# 12_DDR2.net
KiCad netlist of a schematic drawn in Altium Designer
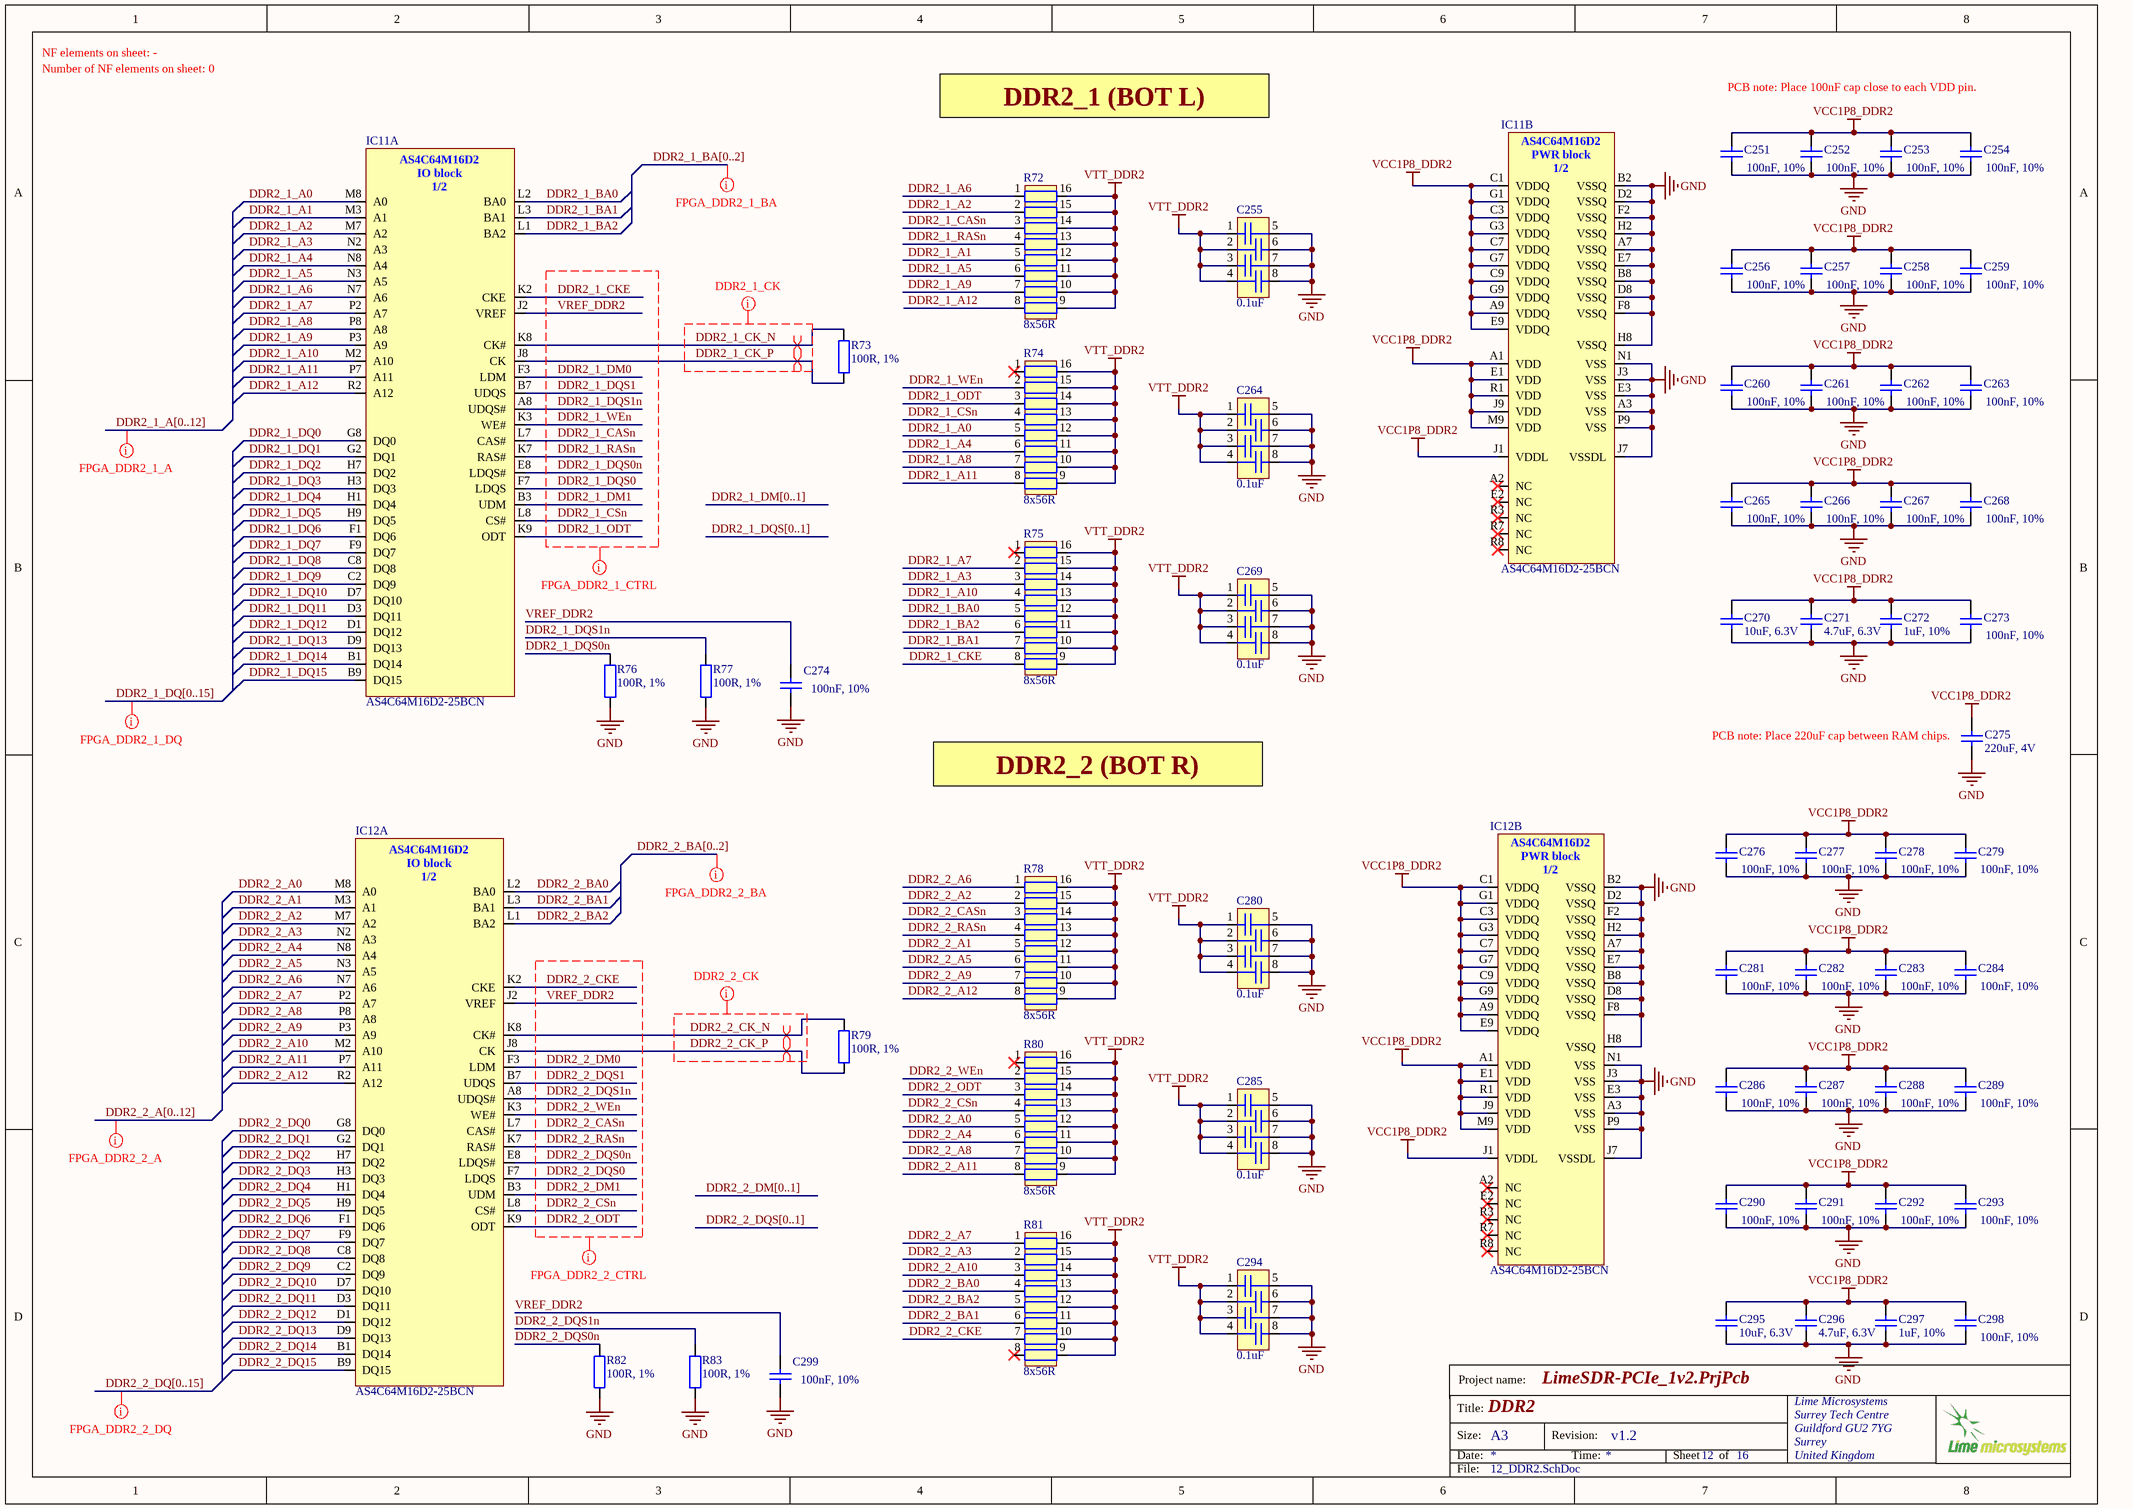
[diagram p0: 12_DDR2.SchDoc]

(export (version "E")
  (design (tool "Eeschema 10.0.6"))
  (components
    (comp (ref "C251")
      (value "100nF, 10%")
      (footprint "CAP0402")
      (fields
        (field (name "TOLERANCE") "10 %")
        (field (name "MANUFACTURER") "Murata Electronics")
        (field (name "MANUFACTURER PART NUMBER") "GRM155R71C104KA88D")
      )
      (libsource (lib "LimeFPGAboard_schLib") (part "Cap_0603"))
    )
    (comp (ref "C252")
      (value "100nF, 10%")
      (footprint "CAP0402")
      (fields
        (field (name "TOLERANCE") "10 %")
        (field (name "MANUFACTURER") "Murata Electronics")
        (field (name "MANUFACTURER PART NUMBER") "GRM155R71C104KA88D")
      )
      (libsource (lib "LimeFPGAboard_schLib") (part "Cap_0603"))
    )
    (comp (ref "C253")
      (value "100nF, 10%")
      (footprint "CAP0402")
      (fields
        (field (name "TOLERANCE") "10 %")
        (field (name "MANUFACTURER") "Murata Electronics")
        (field (name "MANUFACTURER PART NUMBER") "GRM155R71C104KA88D")
      )
      (libsource (lib "LimeFPGAboard_schLib") (part "Cap_0603"))
    )
    (comp (ref "C254")
      (value "100nF, 10%")
      (footprint "CAP0402")
      (fields
        (field (name "TOLERANCE") "10 %")
        (field (name "MANUFACTURER") "Murata Electronics")
        (field (name "MANUFACTURER PART NUMBER") "GRM155R71C104KA88D")
      )
      (libsource (lib "LimeFPGAboard_schLib") (part "Cap_0603"))
    )
    (comp (ref "C255")
      (value "0.1uF")
      (footprint "CKCA43X7R1C104M100AA")
      (fields (field (name "MANUFACTURER") "TDK") (field (name "TOLERANCE") "20 %"))
      (libsource (lib "LimeFPGAboard_schLib") (part "4X_cap_array_1206"))
    )
    (comp (ref "C256")
      (value "100nF, 10%")
      (footprint "CAP0402")
      (fields
        (field (name "TOLERANCE") "10 %")
        (field (name "MANUFACTURER") "Murata Electronics")
        (field (name "MANUFACTURER PART NUMBER") "GRM155R71C104KA88D")
      )
      (libsource (lib "LimeFPGAboard_schLib") (part "Cap_0603"))
    )
    (comp (ref "C257")
      (value "100nF, 10%")
      (footprint "CAP0402")
      (fields
        (field (name "TOLERANCE") "10 %")
        (field (name "MANUFACTURER") "Murata Electronics")
        (field (name "MANUFACTURER PART NUMBER") "GRM155R71C104KA88D")
      )
      (libsource (lib "LimeFPGAboard_schLib") (part "Cap_0603"))
    )
    (comp (ref "C258")
      (value "100nF, 10%")
      (footprint "CAP0402")
      (fields
        (field (name "TOLERANCE") "10 %")
        (field (name "MANUFACTURER") "Murata Electronics")
        (field (name "MANUFACTURER PART NUMBER") "GRM155R71C104KA88D")
      )
      (libsource (lib "LimeFPGAboard_schLib") (part "Cap_0603"))
    )
    (comp (ref "C259")
      (value "100nF, 10%")
      (footprint "CAP0402")
      (fields
        (field (name "TOLERANCE") "10 %")
        (field (name "MANUFACTURER") "Murata Electronics")
        (field (name "MANUFACTURER PART NUMBER") "GRM155R71C104KA88D")
      )
      (libsource (lib "LimeFPGAboard_schLib") (part "Cap_0603"))
    )
    (comp (ref "C260")
      (value "100nF, 10%")
      (footprint "CAP0402")
      (fields
        (field (name "TOLERANCE") "10 %")
        (field (name "MANUFACTURER") "Murata Electronics")
        (field (name "MANUFACTURER PART NUMBER") "GRM155R71C104KA88D")
      )
      (libsource (lib "LimeFPGAboard_schLib") (part "Cap_0603"))
    )
    (comp (ref "C261")
      (value "100nF, 10%")
      (footprint "CAP0402")
      (fields
        (field (name "TOLERANCE") "10 %")
        (field (name "MANUFACTURER") "Murata Electronics")
        (field (name "MANUFACTURER PART NUMBER") "GRM155R71C104KA88D")
      )
      (libsource (lib "LimeFPGAboard_schLib") (part "Cap_0603"))
    )
    (comp (ref "C262")
      (value "100nF, 10%")
      (footprint "CAP0402")
      (fields
        (field (name "TOLERANCE") "10 %")
        (field (name "MANUFACTURER") "Murata Electronics")
        (field (name "MANUFACTURER PART NUMBER") "GRM155R71C104KA88D")
      )
      (libsource (lib "LimeFPGAboard_schLib") (part "Cap_0603"))
    )
    (comp (ref "C263")
      (value "100nF, 10%")
      (footprint "CAP0402")
      (fields
        (field (name "TOLERANCE") "10 %")
        (field (name "MANUFACTURER") "Murata Electronics")
        (field (name "MANUFACTURER PART NUMBER") "GRM155R71C104KA88D")
      )
      (libsource (lib "LimeFPGAboard_schLib") (part "Cap_0603"))
    )
    (comp (ref "C264")
      (value "0.1uF")
      (footprint "CKCA43X7R1C104M100AA")
      (fields (field (name "MANUFACTURER") "TDK") (field (name "TOLERANCE") "20 %"))
      (libsource (lib "LimeFPGAboard_schLib") (part "4X_cap_array_1206"))
    )
    (comp (ref "C265")
      (value "100nF, 10%")
      (footprint "CAP0402")
      (fields
        (field (name "TOLERANCE") "10 %")
        (field (name "MANUFACTURER") "Murata Electronics")
        (field (name "MANUFACTURER PART NUMBER") "GRM155R71C104KA88D")
      )
      (libsource (lib "LimeFPGAboard_schLib") (part "Cap_0603"))
    )
    (comp (ref "C266")
      (value "100nF, 10%")
      (footprint "CAP0402")
      (fields
        (field (name "TOLERANCE") "10 %")
        (field (name "MANUFACTURER") "Murata Electronics")
        (field (name "MANUFACTURER PART NUMBER") "GRM155R71C104KA88D")
      )
      (libsource (lib "LimeFPGAboard_schLib") (part "Cap_0603"))
    )
    (comp (ref "C267")
      (value "100nF, 10%")
      (footprint "CAP0402")
      (fields
        (field (name "TOLERANCE") "10 %")
        (field (name "MANUFACTURER") "Murata Electronics")
        (field (name "MANUFACTURER PART NUMBER") "GRM155R71C104KA88D")
      )
      (libsource (lib "LimeFPGAboard_schLib") (part "Cap_0603"))
    )
    (comp (ref "C268")
      (value "100nF, 10%")
      (footprint "CAP0402")
      (fields
        (field (name "TOLERANCE") "10 %")
        (field (name "MANUFACTURER") "Murata Electronics")
        (field (name "MANUFACTURER PART NUMBER") "GRM155R71C104KA88D")
      )
      (libsource (lib "LimeFPGAboard_schLib") (part "Cap_0603"))
    )
    (comp (ref "C269")
      (value "0.1uF")
      (footprint "CKCA43X7R1C104M100AA")
      (fields (field (name "MANUFACTURER") "TDK") (field (name "TOLERANCE") "20 %"))
      (libsource (lib "LimeFPGAboard_schLib") (part "4X_cap_array_1206"))
    )
    (comp (ref "C270")
      (value "10uF, 6.3V")
      (footprint "CAP0603")
      (fields (field (name "TOLERANCE") "±20%") (field (name "MANUFACTURER") "Yageo"))
      (libsource (lib "LimeFPGAboard_schLib") (part "Cap_0603"))
    )
    (comp (ref "C271")
      (value "4.7uF, 6.3V")
      (footprint "CAP0402")
      (fields
        (field (name "MANUFACTURER") "Murata Electronics North America")
        (field (name "TOLERANCE") "±20%")
      )
      (libsource (lib "LimeMicroAltiumLib_schLib") (part "Cap_0402"))
    )
    (comp (ref "C272")
      (value "1uF, 10%")
      (footprint "CAP0402")
      (fields (field (name "MANUFACTURER") "TDK"))
      (libsource (lib "LimeMicroAltiumLib_schLib") (part "Cap_0402"))
    )
    (comp (ref "C273")
      (value "100nF, 10%")
      (footprint "CAP0402")
      (fields
        (field (name "TOLERANCE") "10 %")
        (field (name "MANUFACTURER") "Murata Electronics")
        (field (name "MANUFACTURER PART NUMBER") "GRM155R71C104KA88D")
      )
      (libsource (lib "LimeFPGAboard_schLib") (part "Cap_0603"))
    )
    (comp (ref "C274")
      (value "100nF, 10%")
      (footprint "CAP0402")
      (fields
        (field (name "TOLERANCE") "10 %")
        (field (name "MANUFACTURER") "Murata Electronics")
        (field (name "MANUFACTURER PART NUMBER") "GRM155R71C104KA88D")
      )
      (libsource (lib "LimeFPGAboard_schLib") (part "Cap_0603"))
    )
    (comp (ref "C275")
      (value "220uF, 4V")
      (footprint "CAP1206")
      (fields
        (field (name "MANUFACTURER PART NUMBER") "GRM31CR60G227ME11L")
        (field (name "MANUFACTURER") "Murata Electronics North America")
        (field (name "TOLERANCE") "±20%")
      )
      (libsource (lib "LimeFPGAboard_schLib") (part "Cap_1206"))
    )
    (comp (ref "C276")
      (value "100nF, 10%")
      (footprint "CAP0402")
      (fields
        (field (name "TOLERANCE") "10 %")
        (field (name "MANUFACTURER") "Murata Electronics")
        (field (name "MANUFACTURER PART NUMBER") "GRM155R71C104KA88D")
      )
      (libsource (lib "LimeFPGAboard_schLib") (part "Cap_0603"))
    )
    (comp (ref "C277")
      (value "100nF, 10%")
      (footprint "CAP0402")
      (fields
        (field (name "TOLERANCE") "10 %")
        (field (name "MANUFACTURER") "Murata Electronics")
        (field (name "MANUFACTURER PART NUMBER") "GRM155R71C104KA88D")
      )
      (libsource (lib "LimeFPGAboard_schLib") (part "Cap_0603"))
    )
    (comp (ref "C278")
      (value "100nF, 10%")
      (footprint "CAP0402")
      (fields
        (field (name "TOLERANCE") "10 %")
        (field (name "MANUFACTURER") "Murata Electronics")
        (field (name "MANUFACTURER PART NUMBER") "GRM155R71C104KA88D")
      )
      (libsource (lib "LimeFPGAboard_schLib") (part "Cap_0603"))
    )
    (comp (ref "C279")
      (value "100nF, 10%")
      (footprint "CAP0402")
      (fields
        (field (name "TOLERANCE") "10 %")
        (field (name "MANUFACTURER") "Murata Electronics")
        (field (name "MANUFACTURER PART NUMBER") "GRM155R71C104KA88D")
      )
      (libsource (lib "LimeFPGAboard_schLib") (part "Cap_0603"))
    )
    (comp (ref "C280")
      (value "0.1uF")
      (footprint "CKCA43X7R1C104M100AA")
      (fields (field (name "MANUFACTURER") "TDK") (field (name "TOLERANCE") "20 %"))
      (libsource (lib "LimeFPGAboard_schLib") (part "4X_cap_array_1206"))
    )
    (comp (ref "C281")
      (value "100nF, 10%")
      (footprint "CAP0402")
      (fields
        (field (name "TOLERANCE") "10 %")
        (field (name "MANUFACTURER") "Murata Electronics")
        (field (name "MANUFACTURER PART NUMBER") "GRM155R71C104KA88D")
      )
      (libsource (lib "LimeFPGAboard_schLib") (part "Cap_0603"))
    )
    (comp (ref "C282")
      (value "100nF, 10%")
      (footprint "CAP0402")
      (fields
        (field (name "TOLERANCE") "10 %")
        (field (name "MANUFACTURER") "Murata Electronics")
        (field (name "MANUFACTURER PART NUMBER") "GRM155R71C104KA88D")
      )
      (libsource (lib "LimeFPGAboard_schLib") (part "Cap_0603"))
    )
    (comp (ref "C283")
      (value "100nF, 10%")
      (footprint "CAP0402")
      (fields
        (field (name "TOLERANCE") "10 %")
        (field (name "MANUFACTURER") "Murata Electronics")
        (field (name "MANUFACTURER PART NUMBER") "GRM155R71C104KA88D")
      )
      (libsource (lib "LimeFPGAboard_schLib") (part "Cap_0603"))
    )
    (comp (ref "C284")
      (value "100nF, 10%")
      (footprint "CAP0402")
      (fields
        (field (name "TOLERANCE") "10 %")
        (field (name "MANUFACTURER") "Murata Electronics")
        (field (name "MANUFACTURER PART NUMBER") "GRM155R71C104KA88D")
      )
      (libsource (lib "LimeFPGAboard_schLib") (part "Cap_0603"))
    )
    (comp (ref "C285")
      (value "0.1uF")
      (footprint "CKCA43X7R1C104M100AA")
      (fields (field (name "MANUFACTURER") "TDK") (field (name "TOLERANCE") "20 %"))
      (libsource (lib "LimeFPGAboard_schLib") (part "4X_cap_array_1206"))
    )
    (comp (ref "C286")
      (value "100nF, 10%")
      (footprint "CAP0402")
      (fields
        (field (name "TOLERANCE") "10 %")
        (field (name "MANUFACTURER") "Murata Electronics")
        (field (name "MANUFACTURER PART NUMBER") "GRM155R71C104KA88D")
      )
      (libsource (lib "LimeFPGAboard_schLib") (part "Cap_0603"))
    )
    (comp (ref "C287")
      (value "100nF, 10%")
      (footprint "CAP0402")
      (fields
        (field (name "TOLERANCE") "10 %")
        (field (name "MANUFACTURER") "Murata Electronics")
        (field (name "MANUFACTURER PART NUMBER") "GRM155R71C104KA88D")
      )
      (libsource (lib "LimeFPGAboard_schLib") (part "Cap_0603"))
    )
    (comp (ref "C288")
      (value "100nF, 10%")
      (footprint "CAP0402")
      (fields
        (field (name "TOLERANCE") "10 %")
        (field (name "MANUFACTURER") "Murata Electronics")
        (field (name "MANUFACTURER PART NUMBER") "GRM155R71C104KA88D")
      )
      (libsource (lib "LimeFPGAboard_schLib") (part "Cap_0603"))
    )
    (comp (ref "C289")
      (value "100nF, 10%")
      (footprint "CAP0402")
      (fields
        (field (name "TOLERANCE") "10 %")
        (field (name "MANUFACTURER") "Murata Electronics")
        (field (name "MANUFACTURER PART NUMBER") "GRM155R71C104KA88D")
      )
      (libsource (lib "LimeFPGAboard_schLib") (part "Cap_0603"))
    )
    (comp (ref "C290")
      (value "100nF, 10%")
      (footprint "CAP0402")
      (fields
        (field (name "TOLERANCE") "10 %")
        (field (name "MANUFACTURER") "Murata Electronics")
        (field (name "MANUFACTURER PART NUMBER") "GRM155R71C104KA88D")
      )
      (libsource (lib "LimeFPGAboard_schLib") (part "Cap_0603"))
    )
    (comp (ref "C291")
      (value "100nF, 10%")
      (footprint "CAP0402")
      (fields
        (field (name "TOLERANCE") "10 %")
        (field (name "MANUFACTURER") "Murata Electronics")
        (field (name "MANUFACTURER PART NUMBER") "GRM155R71C104KA88D")
      )
      (libsource (lib "LimeFPGAboard_schLib") (part "Cap_0603"))
    )
    (comp (ref "C292")
      (value "100nF, 10%")
      (footprint "CAP0402")
      (fields
        (field (name "TOLERANCE") "10 %")
        (field (name "MANUFACTURER") "Murata Electronics")
        (field (name "MANUFACTURER PART NUMBER") "GRM155R71C104KA88D")
      )
      (libsource (lib "LimeFPGAboard_schLib") (part "Cap_0603"))
    )
    (comp (ref "C293")
      (value "100nF, 10%")
      (footprint "CAP0402")
      (fields
        (field (name "TOLERANCE") "10 %")
        (field (name "MANUFACTURER") "Murata Electronics")
        (field (name "MANUFACTURER PART NUMBER") "GRM155R71C104KA88D")
      )
      (libsource (lib "LimeFPGAboard_schLib") (part "Cap_0603"))
    )
    (comp (ref "C294")
      (value "0.1uF")
      (footprint "CKCA43X7R1C104M100AA")
      (fields (field (name "MANUFACTURER") "TDK") (field (name "TOLERANCE") "20 %"))
      (libsource (lib "LimeFPGAboard_schLib") (part "4X_cap_array_1206"))
    )
    (comp (ref "C295")
      (value "10uF, 6.3V")
      (footprint "CAP0603")
      (fields (field (name "TOLERANCE") "±20%") (field (name "MANUFACTURER") "Yageo"))
      (libsource (lib "LimeFPGAboard_schLib") (part "Cap_0603"))
    )
    (comp (ref "C296")
      (value "4.7uF, 6.3V")
      (footprint "CAP0402")
      (fields
        (field (name "MANUFACTURER") "Murata Electronics North America")
        (field (name "TOLERANCE") "±20%")
      )
      (libsource (lib "LimeMicroAltiumLib_schLib") (part "Cap_0402"))
    )
    (comp (ref "C297")
      (value "1uF, 10%")
      (footprint "CAP0402")
      (fields (field (name "MANUFACTURER") "TDK"))
      (libsource (lib "LimeMicroAltiumLib_schLib") (part "Cap_0402"))
    )
    (comp (ref "C298")
      (value "100nF, 10%")
      (footprint "CAP0402")
      (fields
        (field (name "TOLERANCE") "10 %")
        (field (name "MANUFACTURER") "Murata Electronics")
        (field (name "MANUFACTURER PART NUMBER") "GRM155R71C104KA88D")
      )
      (libsource (lib "LimeFPGAboard_schLib") (part "Cap_0603"))
    )
    (comp (ref "C299")
      (value "100nF, 10%")
      (footprint "CAP0402")
      (fields
        (field (name "TOLERANCE") "10 %")
        (field (name "MANUFACTURER") "Murata Electronics")
        (field (name "MANUFACTURER PART NUMBER") "GRM155R71C104KA88D")
      )
      (libsource (lib "LimeFPGAboard_schLib") (part "Cap_0603"))
    )
    (comp (ref "IC11")
      (value "AS4C64M16D2-25BCN")
      (footprint "AS4C64M16D2")
      (fields (field (name "MANUFACTURER") "Alliance Memory, Inc."))
      (libsource (lib "LimeMicroAltiumLib_schLib") (part "AS4C64M16D2-25BCN"))
    )
    (comp (ref "IC12")
      (value "AS4C64M16D2-25BCN")
      (footprint "AS4C64M16D2")
      (fields (field (name "MANUFACTURER") "Alliance Memory, Inc."))
      (libsource (lib "LimeMicroAltiumLib_schLib") (part "AS4C64M16D2-25BCN"))
    )
    (comp (ref "R72")
      (value "8x56R")
      (footprint "EXB2HV")
      (fields (field (name "MANUFACTURER") "PANASONIC ELECTRONIC COMPONENTS"))
      (libsource (lib "LimeFPGAboard_schLib") (part "8X_resistor_array_0402"))
    )
    (comp (ref "R73")
      (value "100R, 1%")
      (footprint "RES0402")
      (fields (field (name "TOLERANCE") "±1%") (field (name "MANUFACTURER") "Stackpole Electronics Inc."))
      (libsource (lib "LimeFPGAboard_schLib") (part "Res_0402"))
    )
    (comp (ref "R74")
      (value "8x56R")
      (footprint "EXB2HV")
      (fields (field (name "MANUFACTURER") "PANASONIC ELECTRONIC COMPONENTS"))
      (libsource (lib "LimeFPGAboard_schLib") (part "8X_resistor_array_0402"))
    )
    (comp (ref "R75")
      (value "8x56R")
      (footprint "EXB2HV")
      (fields (field (name "MANUFACTURER") "PANASONIC ELECTRONIC COMPONENTS"))
      (libsource (lib "LimeFPGAboard_schLib") (part "8X_resistor_array_0402"))
    )
    (comp (ref "R76")
      (value "100R, 1%")
      (footprint "RES0402")
      (fields (field (name "TOLERANCE") "±1%") (field (name "MANUFACTURER") "Stackpole Electronics Inc."))
      (libsource (lib "LimeFPGAboard_schLib") (part "Res_0402"))
    )
    (comp (ref "R77")
      (value "100R, 1%")
      (footprint "RES0402")
      (fields (field (name "TOLERANCE") "±1%") (field (name "MANUFACTURER") "Stackpole Electronics Inc."))
      (libsource (lib "LimeFPGAboard_schLib") (part "Res_0402"))
    )
    (comp (ref "R78")
      (value "8x56R")
      (footprint "EXB2HV")
      (fields (field (name "MANUFACTURER") "PANASONIC ELECTRONIC COMPONENTS"))
      (libsource (lib "LimeFPGAboard_schLib") (part "8X_resistor_array_0402"))
    )
    (comp (ref "R79")
      (value "100R, 1%")
      (footprint "RES0402")
      (fields (field (name "TOLERANCE") "±1%") (field (name "MANUFACTURER") "Stackpole Electronics Inc."))
      (libsource (lib "LimeFPGAboard_schLib") (part "Res_0402"))
    )
    (comp (ref "R80")
      (value "8x56R")
      (footprint "EXB2HV")
      (fields (field (name "MANUFACTURER") "PANASONIC ELECTRONIC COMPONENTS"))
      (libsource (lib "LimeFPGAboard_schLib") (part "8X_resistor_array_0402"))
    )
    (comp (ref "R81")
      (value "8x56R")
      (footprint "EXB2HV")
      (fields (field (name "MANUFACTURER") "PANASONIC ELECTRONIC COMPONENTS"))
      (libsource (lib "LimeFPGAboard_schLib") (part "8X_resistor_array_0402"))
    )
    (comp (ref "R82")
      (value "100R, 1%")
      (footprint "RES0402")
      (fields (field (name "TOLERANCE") "±1%") (field (name "MANUFACTURER") "Stackpole Electronics Inc."))
      (libsource (lib "LimeFPGAboard_schLib") (part "Res_0402"))
    )
    (comp (ref "R83")
      (value "100R, 1%")
      (footprint "RES0402")
      (fields (field (name "TOLERANCE") "±1%") (field (name "MANUFACTURER") "Stackpole Electronics Inc."))
      (libsource (lib "LimeFPGAboard_schLib") (part "Res_0402"))
    )
  )
  (nets
    (net (code "1") (name "/DDR2_1_A0") (class "Default")
      (node (ref "IC11") (pin "M8") (pinfunction "A0_M8") (pintype "passive"))
      (node (ref "R74") (pin "5") (pinfunction "5_5") (pintype "passive"))
    )
    (net (code "2") (name "/DDR2_1_A1") (class "Default")
      (node (ref "IC11") (pin "M3") (pinfunction "A1_M3") (pintype "passive"))
      (node (ref "R72") (pin "5") (pinfunction "5_5") (pintype "passive"))
    )
    (net (code "3") (name "/DDR2_1_A2") (class "Default")
      (node (ref "IC11") (pin "M7") (pinfunction "A2_M7") (pintype "passive"))
      (node (ref "R72") (pin "2") (pinfunction "2_2") (pintype "passive"))
    )
    (net (code "4") (name "/DDR2_1_A3") (class "Default")
      (node (ref "IC11") (pin "N2") (pinfunction "A3_N2") (pintype "passive"))
      (node (ref "R75") (pin "3") (pinfunction "3_3") (pintype "passive"))
    )
    (net (code "5") (name "/DDR2_1_A4") (class "Default")
      (node (ref "IC11") (pin "N8") (pinfunction "A4_N8") (pintype "passive"))
      (node (ref "R74") (pin "6") (pinfunction "6_6") (pintype "passive"))
    )
    (net (code "6") (name "/DDR2_1_A5") (class "Default")
      (node (ref "IC11") (pin "N3") (pinfunction "A5_N3") (pintype "passive"))
      (node (ref "R72") (pin "6") (pinfunction "6_6") (pintype "passive"))
    )
    (net (code "7") (name "/DDR2_1_A6") (class "Default")
      (node (ref "IC11") (pin "N7") (pinfunction "A6_N7") (pintype "passive"))
      (node (ref "R72") (pin "1") (pinfunction "1_1") (pintype "passive"))
    )
    (net (code "8") (name "/DDR2_1_A7") (class "Default")
      (node (ref "IC11") (pin "P2") (pinfunction "A7_P2") (pintype "passive"))
      (node (ref "R75") (pin "2") (pinfunction "2_2") (pintype "passive"))
    )
    (net (code "9") (name "/DDR2_1_A8") (class "Default")
      (node (ref "IC11") (pin "P8") (pinfunction "A8_P8") (pintype "passive"))
      (node (ref "R74") (pin "7") (pinfunction "7_7") (pintype "passive"))
    )
    (net (code "10") (name "/DDR2_1_A9") (class "Default")
      (node (ref "IC11") (pin "P3") (pinfunction "A9_P3") (pintype "passive"))
      (node (ref "R72") (pin "7") (pinfunction "7_7") (pintype "passive"))
    )
    (net (code "11") (name "/DDR2_1_A10") (class "Default")
      (node (ref "IC11") (pin "M2") (pinfunction "A10_M2") (pintype "passive"))
      (node (ref "R75") (pin "4") (pinfunction "4_4") (pintype "passive"))
    )
    (net (code "12") (name "/DDR2_1_A11") (class "Default")
      (node (ref "IC11") (pin "P7") (pinfunction "A11_P7") (pintype "passive"))
      (node (ref "R74") (pin "8") (pinfunction "8_8") (pintype "passive"))
    )
    (net (code "13") (name "/DDR2_1_A12") (class "Default")
      (node (ref "IC11") (pin "R2") (pinfunction "A12_R2") (pintype "passive"))
      (node (ref "R72") (pin "8") (pinfunction "8_8") (pintype "passive"))
    )
    (net (code "15") (name "/DDR2_1_BA0") (class "Default")
      (node (ref "IC11") (pin "L2") (pinfunction "BA0_L2") (pintype "passive"))
      (node (ref "R75") (pin "5") (pinfunction "5_5") (pintype "passive"))
    )
    (net (code "16") (name "/DDR2_1_BA1") (class "Default")
      (node (ref "IC11") (pin "L3") (pinfunction "BA1_L3") (pintype "passive"))
      (node (ref "R75") (pin "7") (pinfunction "7_7") (pintype "passive"))
    )
    (net (code "17") (name "/DDR2_1_BA2") (class "Default")
      (node (ref "IC11") (pin "L1") (pinfunction "BA2_L1") (pintype "passive"))
      (node (ref "R75") (pin "6") (pinfunction "6_6") (pintype "passive"))
    )
    (net (code "19") (name "/DDR2_1_CASn") (class "Default")
      (node (ref "IC11") (pin "L7") (pinfunction "CAS#_L7") (pintype "passive"))
      (node (ref "R72") (pin "3") (pinfunction "3_3") (pintype "passive"))
    )
    (net (code "20") (name "/DDR2_1_CKE") (class "Default")
      (node (ref "IC11") (pin "K2") (pinfunction "CKE_K2") (pintype "passive"))
      (node (ref "R75") (pin "8") (pinfunction "8_8") (pintype "passive"))
    )
    (net (code "21") (name "/DDR2_1_CK_N") (class "Default")
      (node (ref "IC11") (pin "K8") (pinfunction "CK#_K8") (pintype "passive"))
      (node (ref "R73") (pin "2") (pinfunction "2_2") (pintype "passive"))
    )
    (net (code "22") (name "/DDR2_1_CK_P") (class "Default")
      (node (ref "IC11") (pin "J8") (pinfunction "CK_J8") (pintype "passive"))
      (node (ref "R73") (pin "1") (pinfunction "1_1") (pintype "passive"))
    )
    (net (code "23") (name "/DDR2_1_CSn") (class "Default")
      (node (ref "IC11") (pin "L8") (pinfunction "CS#_L8") (pintype "passive"))
      (node (ref "R74") (pin "4") (pinfunction "4_4") (pintype "passive"))
    )
    (net (code "24") (name "/DDR2_1_DM0") (class "Default")
      (node (ref "IC11") (pin "F3") (pinfunction "LDM_F3") (pintype "passive"))
    )
    (net (code "25") (name "/DDR2_1_DM1") (class "Default")
      (node (ref "IC11") (pin "B3") (pinfunction "UDM_B3") (pintype "passive"))
    )
    (net (code "27") (name "/DDR2_1_DQ0") (class "Default")
      (node (ref "IC11") (pin "G8") (pinfunction "DQ0_G8") (pintype "passive"))
    )
    (net (code "28") (name "/DDR2_1_DQ1") (class "Default")
      (node (ref "IC11") (pin "G2") (pinfunction "DQ1_G2") (pintype "passive"))
    )
    (net (code "29") (name "/DDR2_1_DQ2") (class "Default")
      (node (ref "IC11") (pin "H7") (pinfunction "DQ2_H7") (pintype "passive"))
    )
    (net (code "30") (name "/DDR2_1_DQ3") (class "Default")
      (node (ref "IC11") (pin "H3") (pinfunction "DQ3_H3") (pintype "passive"))
    )
    (net (code "31") (name "/DDR2_1_DQ4") (class "Default")
      (node (ref "IC11") (pin "H1") (pinfunction "DQ4_H1") (pintype "passive"))
    )
    (net (code "32") (name "/DDR2_1_DQ5") (class "Default")
      (node (ref "IC11") (pin "H9") (pinfunction "DQ5_H9") (pintype "passive"))
    )
    (net (code "33") (name "/DDR2_1_DQ6") (class "Default")
      (node (ref "IC11") (pin "F1") (pinfunction "DQ6_F1") (pintype "passive"))
    )
    (net (code "34") (name "/DDR2_1_DQ7") (class "Default")
      (node (ref "IC11") (pin "F9") (pinfunction "DQ7_F9") (pintype "passive"))
    )
    (net (code "35") (name "/DDR2_1_DQ8") (class "Default")
      (node (ref "IC11") (pin "C8") (pinfunction "DQ8_C8") (pintype "passive"))
    )
    (net (code "36") (name "/DDR2_1_DQ9") (class "Default")
      (node (ref "IC11") (pin "C2") (pinfunction "DQ9_C2") (pintype "passive"))
    )
    (net (code "37") (name "/DDR2_1_DQ10") (class "Default")
      (node (ref "IC11") (pin "D7") (pinfunction "DQ10_D7") (pintype "passive"))
    )
    (net (code "38") (name "/DDR2_1_DQ11") (class "Default")
      (node (ref "IC11") (pin "D3") (pinfunction "DQ11_D3") (pintype "passive"))
    )
    (net (code "39") (name "/DDR2_1_DQ12") (class "Default")
      (node (ref "IC11") (pin "D1") (pinfunction "DQ12_D1") (pintype "passive"))
    )
    (net (code "40") (name "/DDR2_1_DQ13") (class "Default")
      (node (ref "IC11") (pin "D9") (pinfunction "DQ13_D9") (pintype "passive"))
    )
    (net (code "41") (name "/DDR2_1_DQ14") (class "Default")
      (node (ref "IC11") (pin "B1") (pinfunction "DQ14_B1") (pintype "passive"))
    )
    (net (code "42") (name "/DDR2_1_DQ15") (class "Default")
      (node (ref "IC11") (pin "B9") (pinfunction "DQ15_B9") (pintype "passive"))
    )
    (net (code "43") (name "/DDR2_1_DQS0") (class "Default")
      (node (ref "IC11") (pin "F7") (pinfunction "LDQS_F7") (pintype "passive"))
    )
    (net (code "44") (name "/DDR2_1_DQS0n") (class "Default")
      (node (ref "IC11") (pin "E8") (pinfunction "LDQS#_E8") (pintype "passive"))
      (node (ref "R76") (pin "2") (pinfunction "2_2") (pintype "passive"))
    )
    (net (code "45") (name "/DDR2_1_DQS1") (class "Default")
      (node (ref "IC11") (pin "B7") (pinfunction "UDQS_B7") (pintype "passive"))
    )
    (net (code "46") (name "/DDR2_1_DQS1n") (class "Default")
      (node (ref "IC11") (pin "A8") (pinfunction "UDQS#_A8") (pintype "passive"))
      (node (ref "R77") (pin "2") (pinfunction "2_2") (pintype "passive"))
    )
    (net (code "49") (name "/DDR2_1_ODT") (class "Default")
      (node (ref "IC11") (pin "K9") (pinfunction "ODT_K9") (pintype "passive"))
      (node (ref "R74") (pin "3") (pinfunction "3_3") (pintype "passive"))
    )
    (net (code "50") (name "/DDR2_1_RASn") (class "Default")
      (node (ref "IC11") (pin "K7") (pinfunction "RAS#_K7") (pintype "passive"))
      (node (ref "R72") (pin "4") (pinfunction "4_4") (pintype "passive"))
    )
    (net (code "51") (name "/DDR2_1_WEn") (class "Default")
      (node (ref "IC11") (pin "K3") (pinfunction "WE#_K3") (pintype "passive"))
      (node (ref "R74") (pin "2") (pinfunction "2_2") (pintype "passive"))
    )
    (net (code "52") (name "/DDR2_2_A0") (class "Default")
      (node (ref "IC12") (pin "M8") (pinfunction "A0_M8") (pintype "passive"))
      (node (ref "R80") (pin "5") (pinfunction "5_5") (pintype "passive"))
    )
    (net (code "53") (name "/DDR2_2_A1") (class "Default")
      (node (ref "IC12") (pin "M3") (pinfunction "A1_M3") (pintype "passive"))
      (node (ref "R78") (pin "5") (pinfunction "5_5") (pintype "passive"))
    )
    (net (code "54") (name "/DDR2_2_A2") (class "Default")
      (node (ref "IC12") (pin "M7") (pinfunction "A2_M7") (pintype "passive"))
      (node (ref "R78") (pin "2") (pinfunction "2_2") (pintype "passive"))
    )
    (net (code "55") (name "/DDR2_2_A3") (class "Default")
      (node (ref "IC12") (pin "N2") (pinfunction "A3_N2") (pintype "passive"))
      (node (ref "R81") (pin "2") (pinfunction "2_2") (pintype "passive"))
    )
    (net (code "56") (name "/DDR2_2_A4") (class "Default")
      (node (ref "IC12") (pin "N8") (pinfunction "A4_N8") (pintype "passive"))
      (node (ref "R80") (pin "6") (pinfunction "6_6") (pintype "passive"))
    )
    (net (code "57") (name "/DDR2_2_A5") (class "Default")
      (node (ref "IC12") (pin "N3") (pinfunction "A5_N3") (pintype "passive"))
      (node (ref "R78") (pin "6") (pinfunction "6_6") (pintype "passive"))
    )
    (net (code "58") (name "/DDR2_2_A6") (class "Default")
      (node (ref "IC12") (pin "N7") (pinfunction "A6_N7") (pintype "passive"))
      (node (ref "R78") (pin "1") (pinfunction "1_1") (pintype "passive"))
    )
    (net (code "59") (name "/DDR2_2_A7") (class "Default")
      (node (ref "IC12") (pin "P2") (pinfunction "A7_P2") (pintype "passive"))
      (node (ref "R81") (pin "1") (pinfunction "1_1") (pintype "passive"))
    )
    (net (code "60") (name "/DDR2_2_A8") (class "Default")
      (node (ref "IC12") (pin "P8") (pinfunction "A8_P8") (pintype "passive"))
      (node (ref "R80") (pin "7") (pinfunction "7_7") (pintype "passive"))
    )
    (net (code "61") (name "/DDR2_2_A9") (class "Default")
      (node (ref "IC12") (pin "P3") (pinfunction "A9_P3") (pintype "passive"))
      (node (ref "R78") (pin "7") (pinfunction "7_7") (pintype "passive"))
    )
    (net (code "62") (name "/DDR2_2_A10") (class "Default")
      (node (ref "IC12") (pin "M2") (pinfunction "A10_M2") (pintype "passive"))
      (node (ref "R81") (pin "3") (pinfunction "3_3") (pintype "passive"))
    )
    (net (code "63") (name "/DDR2_2_A11") (class "Default")
      (node (ref "IC12") (pin "P7") (pinfunction "A11_P7") (pintype "passive"))
      (node (ref "R80") (pin "8") (pinfunction "8_8") (pintype "passive"))
    )
    (net (code "64") (name "/DDR2_2_A12") (class "Default")
      (node (ref "IC12") (pin "R2") (pinfunction "A12_R2") (pintype "passive"))
      (node (ref "R78") (pin "8") (pinfunction "8_8") (pintype "passive"))
    )
    (net (code "66") (name "/DDR2_2_BA0") (class "Default")
      (node (ref "IC12") (pin "L2") (pinfunction "BA0_L2") (pintype "passive"))
      (node (ref "R81") (pin "4") (pinfunction "4_4") (pintype "passive"))
    )
    (net (code "67") (name "/DDR2_2_BA1") (class "Default")
      (node (ref "IC12") (pin "L3") (pinfunction "BA1_L3") (pintype "passive"))
      (node (ref "R81") (pin "6") (pinfunction "6_6") (pintype "passive"))
    )
    (net (code "68") (name "/DDR2_2_BA2") (class "Default")
      (node (ref "IC12") (pin "L1") (pinfunction "BA2_L1") (pintype "passive"))
      (node (ref "R81") (pin "5") (pinfunction "5_5") (pintype "passive"))
    )
    (net (code "70") (name "/DDR2_2_CASn") (class "Default")
      (node (ref "IC12") (pin "L7") (pinfunction "CAS#_L7") (pintype "passive"))
      (node (ref "R78") (pin "3") (pinfunction "3_3") (pintype "passive"))
    )
    (net (code "71") (name "/DDR2_2_CKE") (class "Default")
      (node (ref "IC12") (pin "K2") (pinfunction "CKE_K2") (pintype "passive"))
      (node (ref "R81") (pin "7") (pinfunction "7_7") (pintype "passive"))
    )
    (net (code "72") (name "/DDR2_2_CK_N") (class "Default")
      (node (ref "IC12") (pin "K8") (pinfunction "CK#_K8") (pintype "passive"))
      (node (ref "R79") (pin "2") (pinfunction "2_2") (pintype "passive"))
    )
    (net (code "73") (name "/DDR2_2_CK_P") (class "Default")
      (node (ref "IC12") (pin "J8") (pinfunction "CK_J8") (pintype "passive"))
      (node (ref "R79") (pin "1") (pinfunction "1_1") (pintype "passive"))
    )
    (net (code "74") (name "/DDR2_2_CSn") (class "Default")
      (node (ref "IC12") (pin "L8") (pinfunction "CS#_L8") (pintype "passive"))
      (node (ref "R80") (pin "4") (pinfunction "4_4") (pintype "passive"))
    )
    (net (code "75") (name "/DDR2_2_DM0") (class "Default")
      (node (ref "IC12") (pin "F3") (pinfunction "LDM_F3") (pintype "passive"))
    )
    (net (code "76") (name "/DDR2_2_DM1") (class "Default")
      (node (ref "IC12") (pin "B3") (pinfunction "UDM_B3") (pintype "passive"))
    )
    (net (code "78") (name "/DDR2_2_DQ0") (class "Default")
      (node (ref "IC12") (pin "G8") (pinfunction "DQ0_G8") (pintype "passive"))
    )
    (net (code "79") (name "/DDR2_2_DQ1") (class "Default")
      (node (ref "IC12") (pin "G2") (pinfunction "DQ1_G2") (pintype "passive"))
    )
    (net (code "80") (name "/DDR2_2_DQ2") (class "Default")
      (node (ref "IC12") (pin "H7") (pinfunction "DQ2_H7") (pintype "passive"))
    )
    (net (code "81") (name "/DDR2_2_DQ3") (class "Default")
      (node (ref "IC12") (pin "H3") (pinfunction "DQ3_H3") (pintype "passive"))
    )
    (net (code "82") (name "/DDR2_2_DQ4") (class "Default")
      (node (ref "IC12") (pin "H1") (pinfunction "DQ4_H1") (pintype "passive"))
    )
    (net (code "83") (name "/DDR2_2_DQ5") (class "Default")
      (node (ref "IC12") (pin "H9") (pinfunction "DQ5_H9") (pintype "passive"))
    )
    (net (code "84") (name "/DDR2_2_DQ6") (class "Default")
      (node (ref "IC12") (pin "F1") (pinfunction "DQ6_F1") (pintype "passive"))
    )
    (net (code "85") (name "/DDR2_2_DQ7") (class "Default")
      (node (ref "IC12") (pin "F9") (pinfunction "DQ7_F9") (pintype "passive"))
    )
    (net (code "86") (name "/DDR2_2_DQ8") (class "Default")
      (node (ref "IC12") (pin "C8") (pinfunction "DQ8_C8") (pintype "passive"))
    )
    (net (code "87") (name "/DDR2_2_DQ9") (class "Default")
      (node (ref "IC12") (pin "C2") (pinfunction "DQ9_C2") (pintype "passive"))
    )
    (net (code "88") (name "/DDR2_2_DQ10") (class "Default")
      (node (ref "IC12") (pin "D7") (pinfunction "DQ10_D7") (pintype "passive"))
    )
    (net (code "89") (name "/DDR2_2_DQ11") (class "Default")
      (node (ref "IC12") (pin "D3") (pinfunction "DQ11_D3") (pintype "passive"))
    )
    (net (code "90") (name "/DDR2_2_DQ12") (class "Default")
      (node (ref "IC12") (pin "D1") (pinfunction "DQ12_D1") (pintype "passive"))
    )
    (net (code "91") (name "/DDR2_2_DQ13") (class "Default")
      (node (ref "IC12") (pin "D9") (pinfunction "DQ13_D9") (pintype "passive"))
    )
    (net (code "92") (name "/DDR2_2_DQ14") (class "Default")
      (node (ref "IC12") (pin "B1") (pinfunction "DQ14_B1") (pintype "passive"))
    )
    (net (code "93") (name "/DDR2_2_DQ15") (class "Default")
      (node (ref "IC12") (pin "B9") (pinfunction "DQ15_B9") (pintype "passive"))
    )
    (net (code "94") (name "/DDR2_2_DQS0") (class "Default")
      (node (ref "IC12") (pin "F7") (pinfunction "LDQS_F7") (pintype "passive"))
    )
    (net (code "95") (name "/DDR2_2_DQS0n") (class "Default")
      (node (ref "IC12") (pin "E8") (pinfunction "LDQS#_E8") (pintype "passive"))
      (node (ref "R82") (pin "2") (pinfunction "2_2") (pintype "passive"))
    )
    (net (code "96") (name "/DDR2_2_DQS1") (class "Default")
      (node (ref "IC12") (pin "B7") (pinfunction "UDQS_B7") (pintype "passive"))
    )
    (net (code "97") (name "/DDR2_2_DQS1n") (class "Default")
      (node (ref "IC12") (pin "A8") (pinfunction "UDQS#_A8") (pintype "passive"))
      (node (ref "R83") (pin "2") (pinfunction "2_2") (pintype "passive"))
    )
    (net (code "100") (name "/DDR2_2_ODT") (class "Default")
      (node (ref "IC12") (pin "K9") (pinfunction "ODT_K9") (pintype "passive"))
      (node (ref "R80") (pin "3") (pinfunction "3_3") (pintype "passive"))
    )
    (net (code "101") (name "/DDR2_2_RASn") (class "Default")
      (node (ref "IC12") (pin "K7") (pinfunction "RAS#_K7") (pintype "passive"))
      (node (ref "R78") (pin "4") (pinfunction "4_4") (pintype "passive"))
    )
    (net (code "102") (name "/DDR2_2_WEn") (class "Default")
      (node (ref "IC12") (pin "K3") (pinfunction "WE#_K3") (pintype "passive"))
      (node (ref "R80") (pin "2") (pinfunction "2_2") (pintype "passive"))
    )
    (net (code "103") (name "/VREF_DDR2") (class "Default")
      (node (ref "C274") (pin "1") (pinfunction "1_1") (pintype "passive"))
      (node (ref "C299") (pin "1") (pinfunction "1_1") (pintype "passive"))
      (node (ref "IC11") (pin "J2") (pinfunction "VREF_J2") (pintype "passive"))
      (node (ref "IC12") (pin "J2") (pinfunction "VREF_J2") (pintype "passive"))
    )
    (net (code "104") (name "GND") (class "Default")
      (node (ref "C251") (pin "2") (pinfunction "2_2") (pintype "passive"))
      (node (ref "C252") (pin "2") (pinfunction "2_2") (pintype "passive"))
      (node (ref "C253") (pin "2") (pinfunction "2_2") (pintype "passive"))
      (node (ref "C254") (pin "2") (pinfunction "2_2") (pintype "passive"))
      (node (ref "C255") (pin "5") (pinfunction "5_5") (pintype "passive"))
      (node (ref "C255") (pin "6") (pinfunction "6_6") (pintype "passive"))
      (node (ref "C255") (pin "7") (pinfunction "7_7") (pintype "passive"))
      (node (ref "C255") (pin "8") (pinfunction "8_8") (pintype "passive"))
      (node (ref "C256") (pin "2") (pinfunction "2_2") (pintype "passive"))
      (node (ref "C257") (pin "2") (pinfunction "2_2") (pintype "passive"))
      (node (ref "C258") (pin "2") (pinfunction "2_2") (pintype "passive"))
      (node (ref "C259") (pin "2") (pinfunction "2_2") (pintype "passive"))
      (node (ref "C260") (pin "2") (pinfunction "2_2") (pintype "passive"))
      (node (ref "C261") (pin "2") (pinfunction "2_2") (pintype "passive"))
      (node (ref "C262") (pin "2") (pinfunction "2_2") (pintype "passive"))
      (node (ref "C263") (pin "2") (pinfunction "2_2") (pintype "passive"))
      (node (ref "C264") (pin "5") (pinfunction "5_5") (pintype "passive"))
      (node (ref "C264") (pin "6") (pinfunction "6_6") (pintype "passive"))
      (node (ref "C264") (pin "7") (pinfunction "7_7") (pintype "passive"))
      (node (ref "C264") (pin "8") (pinfunction "8_8") (pintype "passive"))
      (node (ref "C265") (pin "2") (pinfunction "2_2") (pintype "passive"))
      (node (ref "C266") (pin "2") (pinfunction "2_2") (pintype "passive"))
      (node (ref "C267") (pin "2") (pinfunction "2_2") (pintype "passive"))
      (node (ref "C268") (pin "2") (pinfunction "2_2") (pintype "passive"))
      (node (ref "C269") (pin "5") (pinfunction "5_5") (pintype "passive"))
      (node (ref "C269") (pin "6") (pinfunction "6_6") (pintype "passive"))
      (node (ref "C269") (pin "7") (pinfunction "7_7") (pintype "passive"))
      (node (ref "C269") (pin "8") (pinfunction "8_8") (pintype "passive"))
      (node (ref "C270") (pin "1") (pinfunction "1_1") (pintype "passive"))
      (node (ref "C271") (pin "1") (pinfunction "1_1") (pintype "passive"))
      (node (ref "C272") (pin "1") (pinfunction "1_1") (pintype "passive"))
      (node (ref "C273") (pin "2") (pinfunction "2_2") (pintype "passive"))
      (node (ref "C274") (pin "2") (pinfunction "2_2") (pintype "passive"))
      (node (ref "C275") (pin "1") (pinfunction "1_1") (pintype "passive"))
      (node (ref "C276") (pin "2") (pinfunction "2_2") (pintype "passive"))
      (node (ref "C277") (pin "2") (pinfunction "2_2") (pintype "passive"))
      (node (ref "C278") (pin "2") (pinfunction "2_2") (pintype "passive"))
      (node (ref "C279") (pin "2") (pinfunction "2_2") (pintype "passive"))
      (node (ref "C280") (pin "5") (pinfunction "5_5") (pintype "passive"))
      (node (ref "C280") (pin "6") (pinfunction "6_6") (pintype "passive"))
      (node (ref "C280") (pin "7") (pinfunction "7_7") (pintype "passive"))
      (node (ref "C280") (pin "8") (pinfunction "8_8") (pintype "passive"))
      (node (ref "C281") (pin "2") (pinfunction "2_2") (pintype "passive"))
      (node (ref "C282") (pin "2") (pinfunction "2_2") (pintype "passive"))
      (node (ref "C283") (pin "2") (pinfunction "2_2") (pintype "passive"))
      (node (ref "C284") (pin "2") (pinfunction "2_2") (pintype "passive"))
      (node (ref "C285") (pin "5") (pinfunction "5_5") (pintype "passive"))
      (node (ref "C285") (pin "6") (pinfunction "6_6") (pintype "passive"))
      (node (ref "C285") (pin "7") (pinfunction "7_7") (pintype "passive"))
      (node (ref "C285") (pin "8") (pinfunction "8_8") (pintype "passive"))
      (node (ref "C286") (pin "2") (pinfunction "2_2") (pintype "passive"))
      (node (ref "C287") (pin "2") (pinfunction "2_2") (pintype "passive"))
      (node (ref "C288") (pin "2") (pinfunction "2_2") (pintype "passive"))
      (node (ref "C289") (pin "2") (pinfunction "2_2") (pintype "passive"))
      (node (ref "C290") (pin "2") (pinfunction "2_2") (pintype "passive"))
      (node (ref "C291") (pin "2") (pinfunction "2_2") (pintype "passive"))
      (node (ref "C292") (pin "2") (pinfunction "2_2") (pintype "passive"))
      (node (ref "C293") (pin "2") (pinfunction "2_2") (pintype "passive"))
      (node (ref "C294") (pin "5") (pinfunction "5_5") (pintype "passive"))
      (node (ref "C294") (pin "6") (pinfunction "6_6") (pintype "passive"))
      (node (ref "C294") (pin "7") (pinfunction "7_7") (pintype "passive"))
      (node (ref "C294") (pin "8") (pinfunction "8_8") (pintype "passive"))
      (node (ref "C295") (pin "1") (pinfunction "1_1") (pintype "passive"))
      (node (ref "C296") (pin "1") (pinfunction "1_1") (pintype "passive"))
      (node (ref "C297") (pin "1") (pinfunction "1_1") (pintype "passive"))
      (node (ref "C298") (pin "2") (pinfunction "2_2") (pintype "passive"))
      (node (ref "C299") (pin "2") (pinfunction "2_2") (pintype "passive"))
      (node (ref "IC11") (pin "A3") (pinfunction "VSS_A3") (pintype "power_in"))
      (node (ref "IC11") (pin "A7") (pinfunction "VSSQ_A7") (pintype "power_in"))
      (node (ref "IC11") (pin "B2") (pinfunction "VSSQ_B2") (pintype "power_in"))
      (node (ref "IC11") (pin "B8") (pinfunction "VSSQ_B8") (pintype "power_in"))
      (node (ref "IC11") (pin "D2") (pinfunction "VSSQ_D2") (pintype "power_in"))
      (node (ref "IC11") (pin "D8") (pinfunction "VSSQ_D8") (pintype "power_in"))
      (node (ref "IC11") (pin "E3") (pinfunction "VSS_E3") (pintype "power_in"))
      (node (ref "IC11") (pin "E7") (pinfunction "VSSQ_E7") (pintype "power_in"))
      (node (ref "IC11") (pin "F2") (pinfunction "VSSQ_F2") (pintype "power_in"))
      (node (ref "IC11") (pin "F8") (pinfunction "VSSQ_F8") (pintype "power_in"))
      (node (ref "IC11") (pin "H2") (pinfunction "VSSQ_H2") (pintype "power_in"))
      (node (ref "IC11") (pin "H8") (pinfunction "VSSQ_H8") (pintype "power_in"))
      (node (ref "IC11") (pin "J3") (pinfunction "VSS_J3") (pintype "power_in"))
      (node (ref "IC11") (pin "J7") (pinfunction "VSSDL_J7") (pintype "power_in"))
      (node (ref "IC11") (pin "N1") (pinfunction "VSS_N1") (pintype "power_in"))
      (node (ref "IC11") (pin "P9") (pinfunction "VSS_P9") (pintype "power_in"))
      (node (ref "IC12") (pin "A3") (pinfunction "VSS_A3") (pintype "power_in"))
      (node (ref "IC12") (pin "A7") (pinfunction "VSSQ_A7") (pintype "power_in"))
      (node (ref "IC12") (pin "B2") (pinfunction "VSSQ_B2") (pintype "power_in"))
      (node (ref "IC12") (pin "B8") (pinfunction "VSSQ_B8") (pintype "power_in"))
      (node (ref "IC12") (pin "D2") (pinfunction "VSSQ_D2") (pintype "power_in"))
      (node (ref "IC12") (pin "D8") (pinfunction "VSSQ_D8") (pintype "power_in"))
      (node (ref "IC12") (pin "E3") (pinfunction "VSS_E3") (pintype "power_in"))
      (node (ref "IC12") (pin "E7") (pinfunction "VSSQ_E7") (pintype "power_in"))
      (node (ref "IC12") (pin "F2") (pinfunction "VSSQ_F2") (pintype "power_in"))
      (node (ref "IC12") (pin "F8") (pinfunction "VSSQ_F8") (pintype "power_in"))
      (node (ref "IC12") (pin "H2") (pinfunction "VSSQ_H2") (pintype "power_in"))
      (node (ref "IC12") (pin "H8") (pinfunction "VSSQ_H8") (pintype "power_in"))
      (node (ref "IC12") (pin "J3") (pinfunction "VSS_J3") (pintype "power_in"))
      (node (ref "IC12") (pin "J7") (pinfunction "VSSDL_J7") (pintype "power_in"))
      (node (ref "IC12") (pin "N1") (pinfunction "VSS_N1") (pintype "power_in"))
      (node (ref "IC12") (pin "P9") (pinfunction "VSS_P9") (pintype "power_in"))
      (node (ref "R76") (pin "1") (pinfunction "1_1") (pintype "passive"))
      (node (ref "R77") (pin "1") (pinfunction "1_1") (pintype "passive"))
      (node (ref "R82") (pin "1") (pinfunction "1_1") (pintype "passive"))
      (node (ref "R83") (pin "1") (pinfunction "1_1") (pintype "passive"))
    )
    (net (code "105") (name "VCC1P8_DDR2") (class "Default")
      (node (ref "C251") (pin "1") (pinfunction "1_1") (pintype "passive"))
      (node (ref "C252") (pin "1") (pinfunction "1_1") (pintype "passive"))
      (node (ref "C253") (pin "1") (pinfunction "1_1") (pintype "passive"))
      (node (ref "C254") (pin "1") (pinfunction "1_1") (pintype "passive"))
      (node (ref "C256") (pin "1") (pinfunction "1_1") (pintype "passive"))
      (node (ref "C257") (pin "1") (pinfunction "1_1") (pintype "passive"))
      (node (ref "C258") (pin "1") (pinfunction "1_1") (pintype "passive"))
      (node (ref "C259") (pin "1") (pinfunction "1_1") (pintype "passive"))
      (node (ref "C260") (pin "1") (pinfunction "1_1") (pintype "passive"))
      (node (ref "C261") (pin "1") (pinfunction "1_1") (pintype "passive"))
      (node (ref "C262") (pin "1") (pinfunction "1_1") (pintype "passive"))
      (node (ref "C263") (pin "1") (pinfunction "1_1") (pintype "passive"))
      (node (ref "C265") (pin "1") (pinfunction "1_1") (pintype "passive"))
      (node (ref "C266") (pin "1") (pinfunction "1_1") (pintype "passive"))
      (node (ref "C267") (pin "1") (pinfunction "1_1") (pintype "passive"))
      (node (ref "C268") (pin "1") (pinfunction "1_1") (pintype "passive"))
      (node (ref "C270") (pin "2") (pinfunction "2_2") (pintype "passive"))
      (node (ref "C271") (pin "2") (pinfunction "2_2") (pintype "passive"))
      (node (ref "C272") (pin "2") (pinfunction "2_2") (pintype "passive"))
      (node (ref "C273") (pin "1") (pinfunction "1_1") (pintype "passive"))
      (node (ref "C275") (pin "2") (pinfunction "2_2") (pintype "passive"))
      (node (ref "C276") (pin "1") (pinfunction "1_1") (pintype "passive"))
      (node (ref "C277") (pin "1") (pinfunction "1_1") (pintype "passive"))
      (node (ref "C278") (pin "1") (pinfunction "1_1") (pintype "passive"))
      (node (ref "C279") (pin "1") (pinfunction "1_1") (pintype "passive"))
      (node (ref "C281") (pin "1") (pinfunction "1_1") (pintype "passive"))
      (node (ref "C282") (pin "1") (pinfunction "1_1") (pintype "passive"))
      (node (ref "C283") (pin "1") (pinfunction "1_1") (pintype "passive"))
      (node (ref "C284") (pin "1") (pinfunction "1_1") (pintype "passive"))
      (node (ref "C286") (pin "1") (pinfunction "1_1") (pintype "passive"))
      (node (ref "C287") (pin "1") (pinfunction "1_1") (pintype "passive"))
      (node (ref "C288") (pin "1") (pinfunction "1_1") (pintype "passive"))
      (node (ref "C289") (pin "1") (pinfunction "1_1") (pintype "passive"))
      (node (ref "C290") (pin "1") (pinfunction "1_1") (pintype "passive"))
      (node (ref "C291") (pin "1") (pinfunction "1_1") (pintype "passive"))
      (node (ref "C292") (pin "1") (pinfunction "1_1") (pintype "passive"))
      (node (ref "C293") (pin "1") (pinfunction "1_1") (pintype "passive"))
      (node (ref "C295") (pin "2") (pinfunction "2_2") (pintype "passive"))
      (node (ref "C296") (pin "2") (pinfunction "2_2") (pintype "passive"))
      (node (ref "C297") (pin "2") (pinfunction "2_2") (pintype "passive"))
      (node (ref "C298") (pin "1") (pinfunction "1_1") (pintype "passive"))
      (node (ref "IC11") (pin "A1") (pinfunction "VDD_A1") (pintype "power_in"))
      (node (ref "IC11") (pin "A9") (pinfunction "VDDQ_A9") (pintype "power_in"))
      (node (ref "IC11") (pin "C1") (pinfunction "VDDQ_C1") (pintype "power_in"))
      (node (ref "IC11") (pin "C3") (pinfunction "VDDQ_C3") (pintype "power_in"))
      (node (ref "IC11") (pin "C7") (pinfunction "VDDQ_C7") (pintype "power_in"))
      (node (ref "IC11") (pin "C9") (pinfunction "VDDQ_C9") (pintype "power_in"))
      (node (ref "IC11") (pin "E1") (pinfunction "VDD_E1") (pintype "power_in"))
      (node (ref "IC11") (pin "E9") (pinfunction "VDDQ_E9") (pintype "power_in"))
      (node (ref "IC11") (pin "G1") (pinfunction "VDDQ_G1") (pintype "power_in"))
      (node (ref "IC11") (pin "G3") (pinfunction "VDDQ_G3") (pintype "power_in"))
      (node (ref "IC11") (pin "G7") (pinfunction "VDDQ_G7") (pintype "power_in"))
      (node (ref "IC11") (pin "G9") (pinfunction "VDDQ_G9") (pintype "power_in"))
      (node (ref "IC11") (pin "J1") (pinfunction "VDDL_J1") (pintype "power_in"))
      (node (ref "IC11") (pin "J9") (pinfunction "VDD_J9") (pintype "power_in"))
      (node (ref "IC11") (pin "M9") (pinfunction "VDD_M9") (pintype "power_in"))
      (node (ref "IC11") (pin "R1") (pinfunction "VDD_R1") (pintype "power_in"))
      (node (ref "IC12") (pin "A1") (pinfunction "VDD_A1") (pintype "power_in"))
      (node (ref "IC12") (pin "A9") (pinfunction "VDDQ_A9") (pintype "power_in"))
      (node (ref "IC12") (pin "C1") (pinfunction "VDDQ_C1") (pintype "power_in"))
      (node (ref "IC12") (pin "C3") (pinfunction "VDDQ_C3") (pintype "power_in"))
      (node (ref "IC12") (pin "C7") (pinfunction "VDDQ_C7") (pintype "power_in"))
      (node (ref "IC12") (pin "C9") (pinfunction "VDDQ_C9") (pintype "power_in"))
      (node (ref "IC12") (pin "E1") (pinfunction "VDD_E1") (pintype "power_in"))
      (node (ref "IC12") (pin "E9") (pinfunction "VDDQ_E9") (pintype "power_in"))
      (node (ref "IC12") (pin "G1") (pinfunction "VDDQ_G1") (pintype "power_in"))
      (node (ref "IC12") (pin "G3") (pinfunction "VDDQ_G3") (pintype "power_in"))
      (node (ref "IC12") (pin "G7") (pinfunction "VDDQ_G7") (pintype "power_in"))
      (node (ref "IC12") (pin "G9") (pinfunction "VDDQ_G9") (pintype "power_in"))
      (node (ref "IC12") (pin "J1") (pinfunction "VDDL_J1") (pintype "power_in"))
      (node (ref "IC12") (pin "J9") (pinfunction "VDD_J9") (pintype "power_in"))
      (node (ref "IC12") (pin "M9") (pinfunction "VDD_M9") (pintype "power_in"))
      (node (ref "IC12") (pin "R1") (pinfunction "VDD_R1") (pintype "power_in"))
    )
    (net (code "106") (name "VTT_DDR2") (class "Default")
      (node (ref "C255") (pin "1") (pinfunction "1_1") (pintype "passive"))
      (node (ref "C255") (pin "2") (pinfunction "2_2") (pintype "passive"))
      (node (ref "C255") (pin "3") (pinfunction "3_3") (pintype "passive"))
      (node (ref "C255") (pin "4") (pinfunction "4_4") (pintype "passive"))
      (node (ref "C264") (pin "1") (pinfunction "1_1") (pintype "passive"))
      (node (ref "C264") (pin "2") (pinfunction "2_2") (pintype "passive"))
      (node (ref "C264") (pin "3") (pinfunction "3_3") (pintype "passive"))
      (node (ref "C264") (pin "4") (pinfunction "4_4") (pintype "passive"))
      (node (ref "C269") (pin "1") (pinfunction "1_1") (pintype "passive"))
      (node (ref "C269") (pin "2") (pinfunction "2_2") (pintype "passive"))
      (node (ref "C269") (pin "3") (pinfunction "3_3") (pintype "passive"))
      (node (ref "C269") (pin "4") (pinfunction "4_4") (pintype "passive"))
      (node (ref "C280") (pin "1") (pinfunction "1_1") (pintype "passive"))
      (node (ref "C280") (pin "2") (pinfunction "2_2") (pintype "passive"))
      (node (ref "C280") (pin "3") (pinfunction "3_3") (pintype "passive"))
      (node (ref "C280") (pin "4") (pinfunction "4_4") (pintype "passive"))
      (node (ref "C285") (pin "1") (pinfunction "1_1") (pintype "passive"))
      (node (ref "C285") (pin "2") (pinfunction "2_2") (pintype "passive"))
      (node (ref "C285") (pin "3") (pinfunction "3_3") (pintype "passive"))
      (node (ref "C285") (pin "4") (pinfunction "4_4") (pintype "passive"))
      (node (ref "C294") (pin "1") (pinfunction "1_1") (pintype "passive"))
      (node (ref "C294") (pin "2") (pinfunction "2_2") (pintype "passive"))
      (node (ref "C294") (pin "3") (pinfunction "3_3") (pintype "passive"))
      (node (ref "C294") (pin "4") (pinfunction "4_4") (pintype "passive"))
      (node (ref "R72") (pin "10") (pinfunction "10_10") (pintype "passive"))
      (node (ref "R72") (pin "11") (pinfunction "11_11") (pintype "passive"))
      (node (ref "R72") (pin "12") (pinfunction "12_12") (pintype "passive"))
      (node (ref "R72") (pin "13") (pinfunction "13_13") (pintype "passive"))
      (node (ref "R72") (pin "14") (pinfunction "14_14") (pintype "passive"))
      (node (ref "R72") (pin "15") (pinfunction "15_15") (pintype "passive"))
      (node (ref "R72") (pin "16") (pinfunction "16_16") (pintype "passive"))
      (node (ref "R72") (pin "9") (pinfunction "9_9") (pintype "passive"))
      (node (ref "R74") (pin "10") (pinfunction "10_10") (pintype "passive"))
      (node (ref "R74") (pin "11") (pinfunction "11_11") (pintype "passive"))
      (node (ref "R74") (pin "12") (pinfunction "12_12") (pintype "passive"))
      (node (ref "R74") (pin "13") (pinfunction "13_13") (pintype "passive"))
      (node (ref "R74") (pin "14") (pinfunction "14_14") (pintype "passive"))
      (node (ref "R74") (pin "15") (pinfunction "15_15") (pintype "passive"))
      (node (ref "R74") (pin "16") (pinfunction "16_16") (pintype "passive"))
      (node (ref "R74") (pin "9") (pinfunction "9_9") (pintype "passive"))
      (node (ref "R75") (pin "10") (pinfunction "10_10") (pintype "passive"))
      (node (ref "R75") (pin "11") (pinfunction "11_11") (pintype "passive"))
      (node (ref "R75") (pin "12") (pinfunction "12_12") (pintype "passive"))
      (node (ref "R75") (pin "13") (pinfunction "13_13") (pintype "passive"))
      (node (ref "R75") (pin "14") (pinfunction "14_14") (pintype "passive"))
      (node (ref "R75") (pin "15") (pinfunction "15_15") (pintype "passive"))
      (node (ref "R75") (pin "16") (pinfunction "16_16") (pintype "passive"))
      (node (ref "R75") (pin "9") (pinfunction "9_9") (pintype "passive"))
      (node (ref "R78") (pin "10") (pinfunction "10_10") (pintype "passive"))
      (node (ref "R78") (pin "11") (pinfunction "11_11") (pintype "passive"))
      (node (ref "R78") (pin "12") (pinfunction "12_12") (pintype "passive"))
      (node (ref "R78") (pin "13") (pinfunction "13_13") (pintype "passive"))
      (node (ref "R78") (pin "14") (pinfunction "14_14") (pintype "passive"))
      (node (ref "R78") (pin "15") (pinfunction "15_15") (pintype "passive"))
      (node (ref "R78") (pin "16") (pinfunction "16_16") (pintype "passive"))
      (node (ref "R78") (pin "9") (pinfunction "9_9") (pintype "passive"))
      (node (ref "R80") (pin "10") (pinfunction "10_10") (pintype "passive"))
      (node (ref "R80") (pin "11") (pinfunction "11_11") (pintype "passive"))
      (node (ref "R80") (pin "12") (pinfunction "12_12") (pintype "passive"))
      (node (ref "R80") (pin "13") (pinfunction "13_13") (pintype "passive"))
      (node (ref "R80") (pin "14") (pinfunction "14_14") (pintype "passive"))
      (node (ref "R80") (pin "15") (pinfunction "15_15") (pintype "passive"))
      (node (ref "R80") (pin "16") (pinfunction "16_16") (pintype "passive"))
      (node (ref "R80") (pin "9") (pinfunction "9_9") (pintype "passive"))
      (node (ref "R81") (pin "10") (pinfunction "10_10") (pintype "passive"))
      (node (ref "R81") (pin "11") (pinfunction "11_11") (pintype "passive"))
      (node (ref "R81") (pin "12") (pinfunction "12_12") (pintype "passive"))
      (node (ref "R81") (pin "13") (pinfunction "13_13") (pintype "passive"))
      (node (ref "R81") (pin "14") (pinfunction "14_14") (pintype "passive"))
      (node (ref "R81") (pin "15") (pinfunction "15_15") (pintype "passive"))
      (node (ref "R81") (pin "16") (pinfunction "16_16") (pintype "passive"))
      (node (ref "R81") (pin "9") (pinfunction "9_9") (pintype "passive"))
    )
    (net (code "107") (name "unconnected-(IC11B-NC-PadA2)") (class "Default")
      (node (ref "IC11") (pin "A2") (pinfunction "NC_A2") (pintype "passive+no_connect"))
    )
    (net (code "108") (name "unconnected-(IC11B-NC-PadE2)") (class "Default")
      (node (ref "IC11") (pin "E2") (pinfunction "NC_E2") (pintype "passive+no_connect"))
    )
    (net (code "109") (name "unconnected-(IC11B-NC-PadR3)") (class "Default")
      (node (ref "IC11") (pin "R3") (pinfunction "NC_R3") (pintype "passive+no_connect"))
    )
    (net (code "110") (name "unconnected-(IC11B-NC-PadR7)") (class "Default")
      (node (ref "IC11") (pin "R7") (pinfunction "NC_R7") (pintype "passive+no_connect"))
    )
    (net (code "111") (name "unconnected-(IC11B-NC-PadR8)") (class "Default")
      (node (ref "IC11") (pin "R8") (pinfunction "NC_R8") (pintype "passive+no_connect"))
    )
    (net (code "112") (name "unconnected-(IC12B-NC-PadA2)") (class "Default")
      (node (ref "IC12") (pin "A2") (pinfunction "NC_A2") (pintype "passive+no_connect"))
    )
    (net (code "113") (name "unconnected-(IC12B-NC-PadE2)") (class "Default")
      (node (ref "IC12") (pin "E2") (pinfunction "NC_E2") (pintype "passive+no_connect"))
    )
    (net (code "114") (name "unconnected-(IC12B-NC-PadR3)") (class "Default")
      (node (ref "IC12") (pin "R3") (pinfunction "NC_R3") (pintype "passive+no_connect"))
    )
    (net (code "115") (name "unconnected-(IC12B-NC-PadR7)") (class "Default")
      (node (ref "IC12") (pin "R7") (pinfunction "NC_R7") (pintype "passive+no_connect"))
    )
    (net (code "116") (name "unconnected-(IC12B-NC-PadR8)") (class "Default")
      (node (ref "IC12") (pin "R8") (pinfunction "NC_R8") (pintype "passive+no_connect"))
    )
    (net (code "117") (name "unconnected-(R74-Pad1)") (class "Default")
      (node (ref "R74") (pin "1") (pinfunction "1_1") (pintype "passive+no_connect"))
    )
    (net (code "118") (name "unconnected-(R75-Pad1)") (class "Default")
      (node (ref "R75") (pin "1") (pinfunction "1_1") (pintype "passive+no_connect"))
    )
    (net (code "119") (name "unconnected-(R80-Pad1)") (class "Default")
      (node (ref "R80") (pin "1") (pinfunction "1_1") (pintype "passive+no_connect"))
    )
    (net (code "120") (name "unconnected-(R81-Pad8)") (class "Default")
      (node (ref "R81") (pin "8") (pinfunction "8_8") (pintype "passive+no_connect"))
    )
  )
)
